# SCH_Jerry-Wang-NFC-Card_2024-10-10.net
KiCad netlist of a schematic drawn in EasyEDA
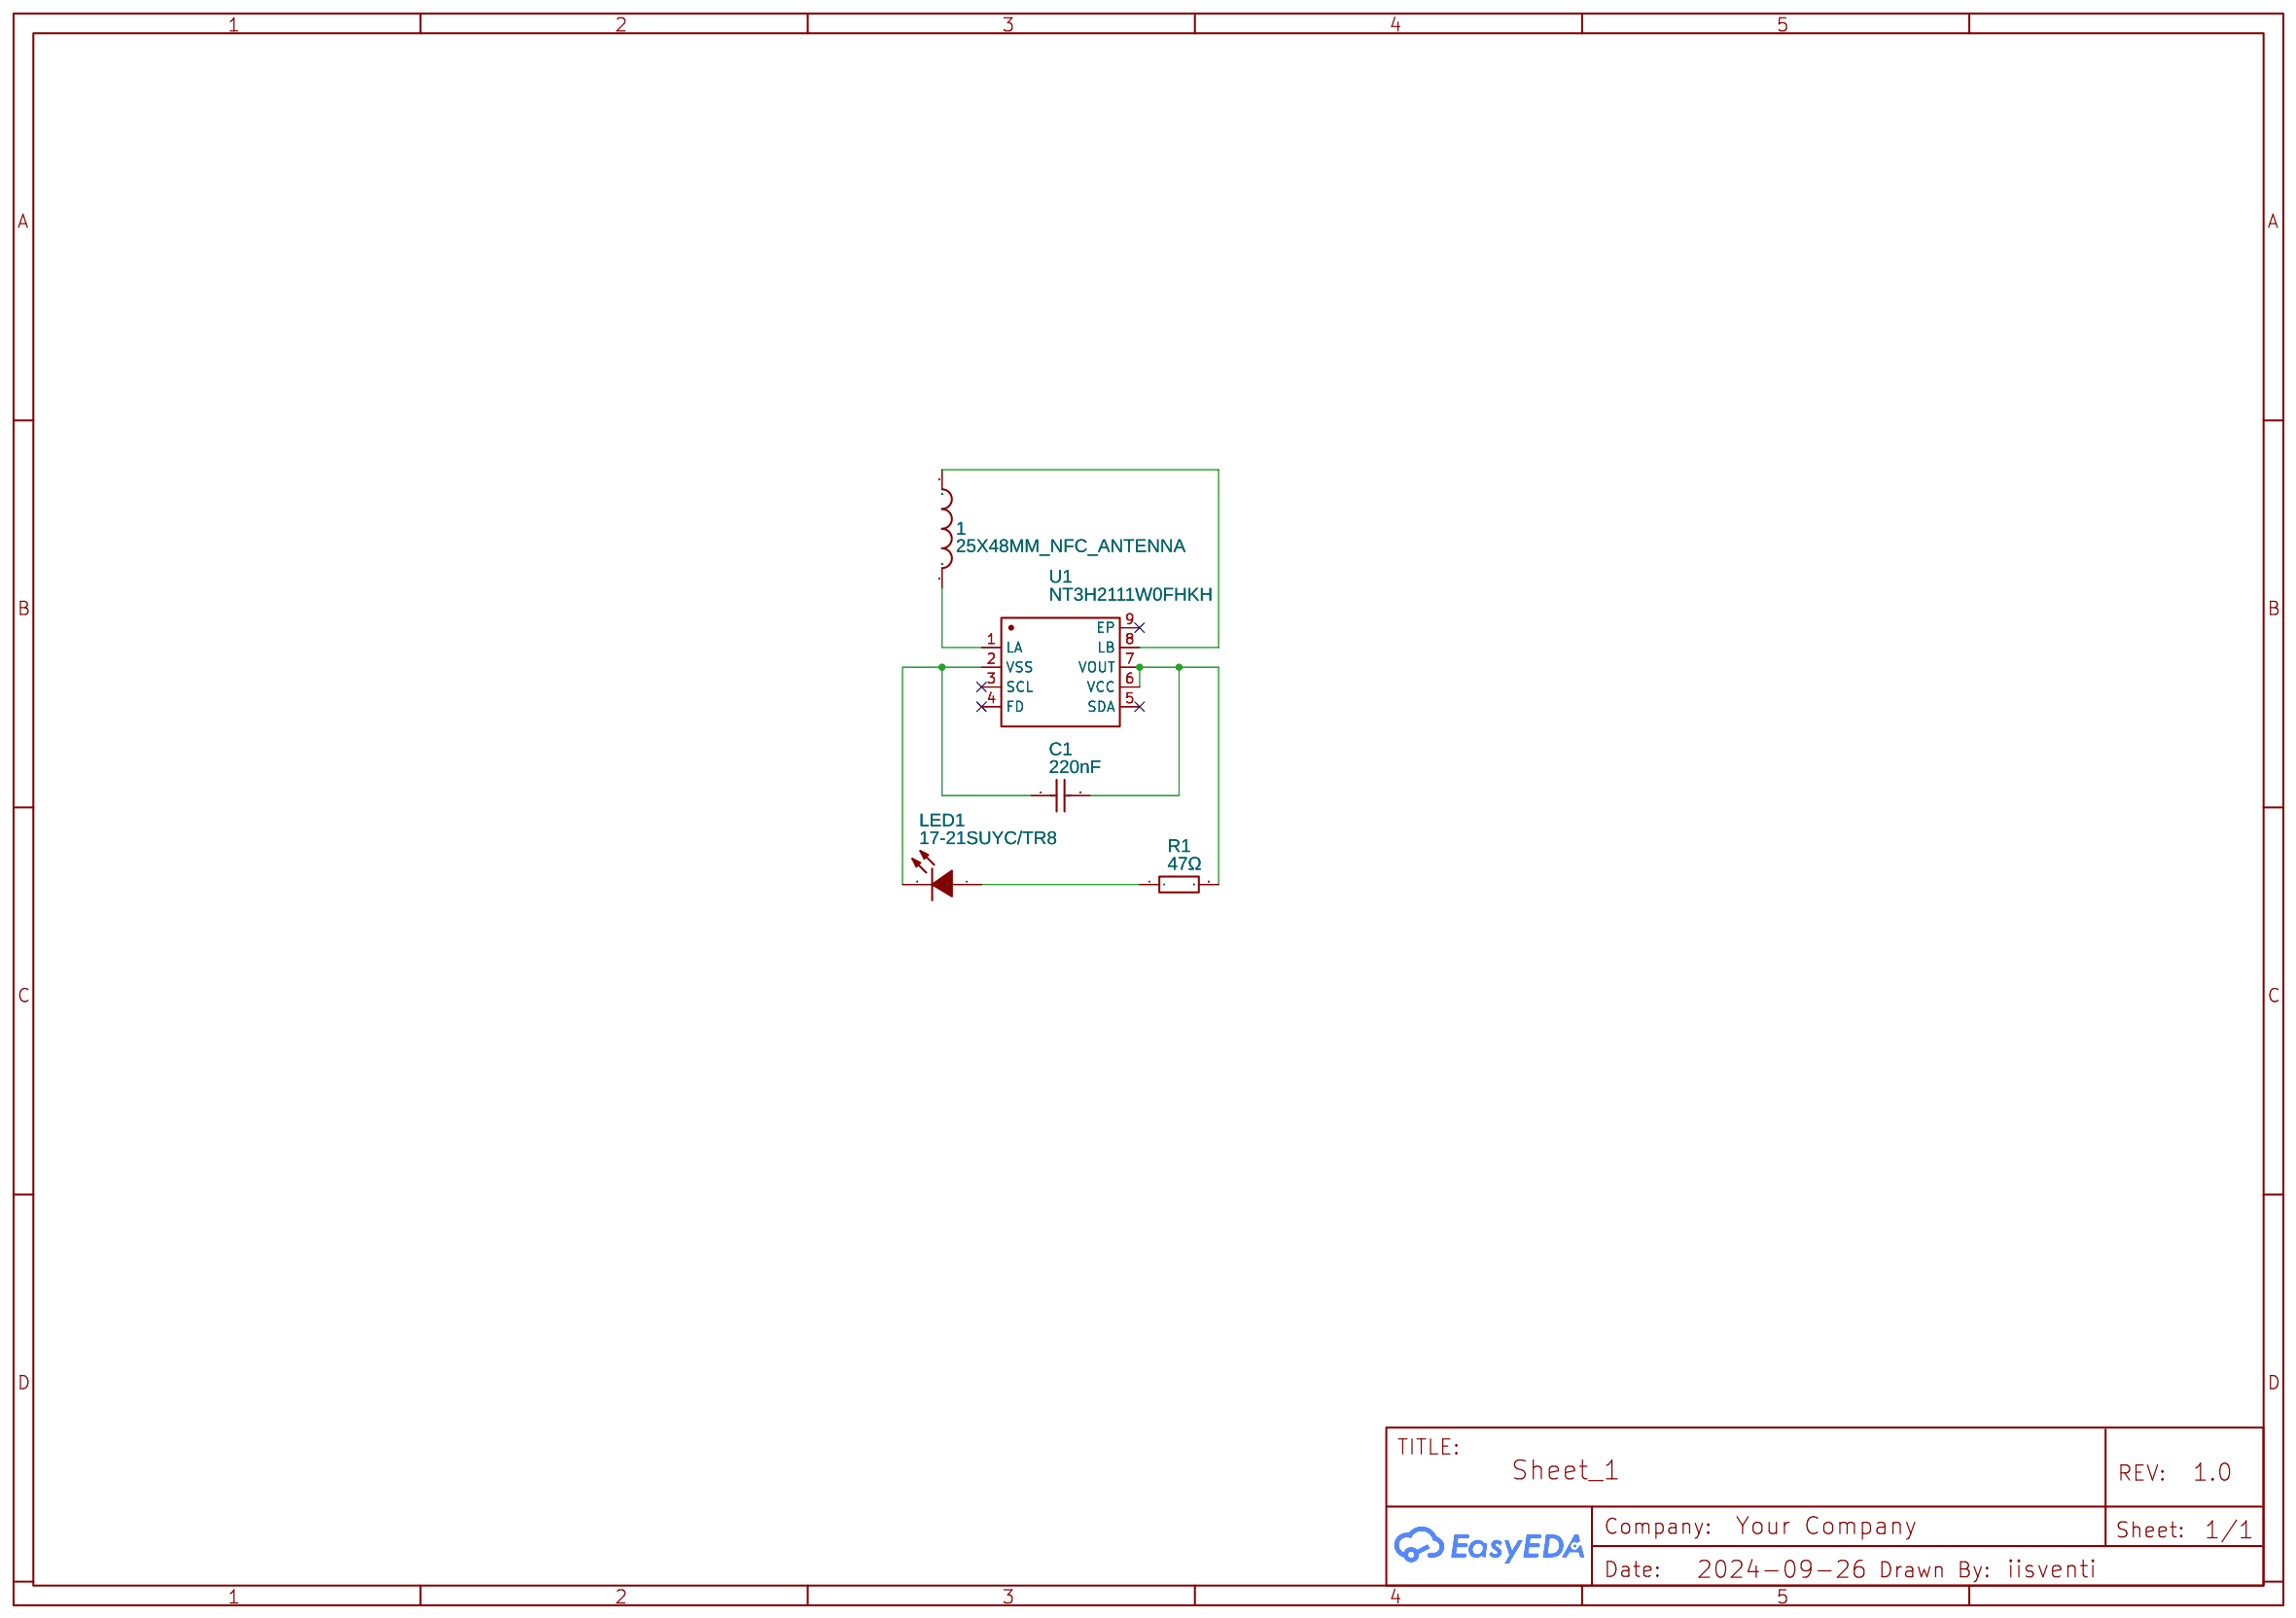
[diagram p0: schematic sheet]

(export (version "E")
  (design (tool "Eeschema 10.0.6"))
  (components
    (comp (ref "1") (value "25X48MM_NFC_ANTENNA") (libsource (lib "") (part "25X48MM_NFC_ANTENNA")))
    (comp (ref "C1")
      (value "220nF")
      (fields
        (field (name "Manufacturer Part") "CL10B224KA8NNNC")
        (field (name "Manufacturer") "SAMSUNG(三星)")
      )
      (libsource (lib "") (part "CL10B224KA8NNNC"))
    )
    (comp (ref "LED1")
      (value "17-21SUYC/TR8")
      (fields (field (name "Manufacturer Part") "KT-0805黄灯") (field (name "Manufacturer") "KENTO"))
      (libsource (lib "") (part "17-21SUYC/TR8"))
    )
    (comp (ref "R1")
      (value "47Ω")
      (fields
        (field (name "Manufacturer Part") "0603WAF470JT5E")
        (field (name "Manufacturer") "UNI-ROYAL(厚声)")
      )
      (libsource (lib "") (part "0603WAF470JT5E"))
    )
    (comp (ref "U1")
      (value "NT3H2111W0FHKH")
      (fields (field (name "Manufacturer") "NXP(恩智浦)"))
      (libsource (lib "") (part "NT3H2111W0FHKH"))
    )
  )
  (nets
    (net (code "1") (name "Net-(LED1-+)") (class "Default")
      (node (ref "LED1") (pin "1") (pinfunction "+_1") (pintype "unspecified"))
      (node (ref "R1") (pin "1") (pinfunction "1_1") (pintype "input"))
    )
    (net (code "2") (name "Net-(LED1--)") (class "Default")
      (node (ref "C1") (pin "1") (pinfunction "1_1") (pintype "input"))
      (node (ref "LED1") (pin "2") (pinfunction "-_2") (pintype "unspecified"))
      (node (ref "U1") (pin "2") (pinfunction "VSS_2") (pintype "unspecified"))
    )
    (net (code "3") (name "Net-(U1-LA)") (class "Default")
      (node (ref "1") (pin "P$2") (pinfunction "P$2_P$2") (pintype "bidirectional"))
      (node (ref "U1") (pin "1") (pinfunction "LA_1") (pintype "unspecified"))
    )
    (net (code "4") (name "Net-(U1-LB)") (class "Default")
      (node (ref "1") (pin "P$1") (pinfunction "P$1_P$1") (pintype "bidirectional"))
      (node (ref "U1") (pin "8") (pinfunction "LB_8") (pintype "unspecified"))
    )
    (net (code "5") (name "Net-(U1-VCC)") (class "Default")
      (node (ref "C1") (pin "2") (pinfunction "2_2") (pintype "input"))
      (node (ref "R1") (pin "2") (pinfunction "2_2") (pintype "input"))
      (node (ref "U1") (pin "6") (pinfunction "VCC_6") (pintype "unspecified"))
      (node (ref "U1") (pin "7") (pinfunction "VOUT_7") (pintype "unspecified"))
    )
    (net (code "6") (name "unconnected-(U1-EP-Pad9)") (class "Default")
      (node (ref "U1") (pin "9") (pinfunction "EP_9") (pintype "unspecified+no_connect"))
    )
    (net (code "7") (name "unconnected-(U1-FD-Pad4)") (class "Default")
      (node (ref "U1") (pin "4") (pinfunction "FD_4") (pintype "unspecified+no_connect"))
    )
    (net (code "8") (name "unconnected-(U1-SCL-Pad3)") (class "Default")
      (node (ref "U1") (pin "3") (pinfunction "SCL_3") (pintype "unspecified+no_connect"))
    )
    (net (code "9") (name "unconnected-(U1-SDA-Pad5)") (class "Default")
      (node (ref "U1") (pin "5") (pinfunction "SDA_5") (pintype "unspecified+no_connect"))
    )
  )
)
